# NT_MCUModule2.net
KiCad netlist of a schematic drawn in EAGLE
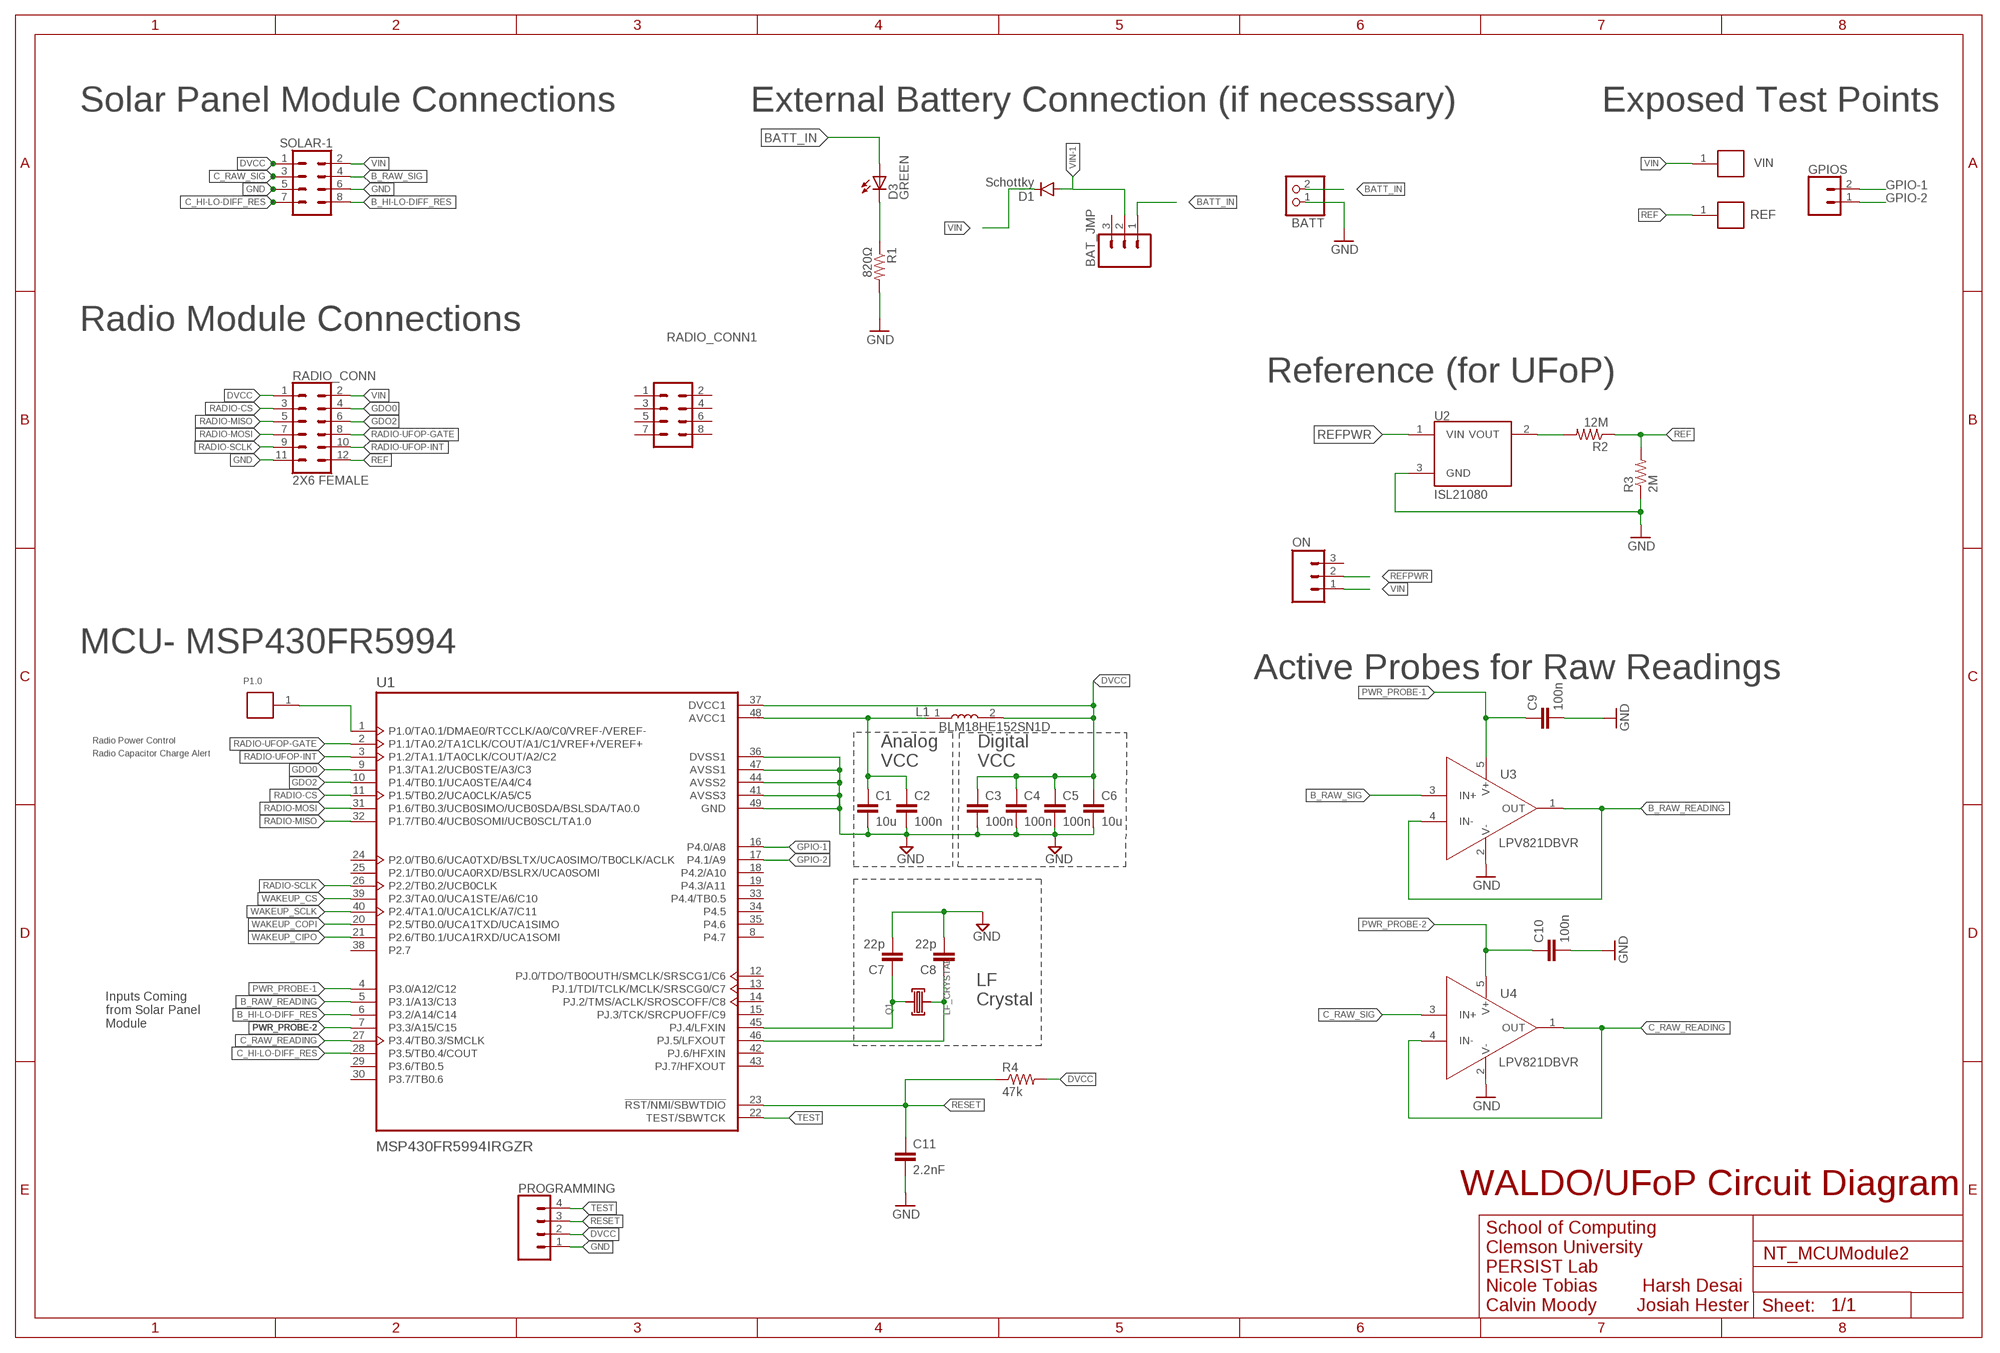
[diagram p0: schematic, sheet 1]

(export (version "E")
  (design (tool "Eeschema 10.0.6"))
  (components
    (comp (ref "BATT")
      (value "PINHD-1X2")
      (footprint "eagle-import:1X02")
      (libsource (lib "eagle-import") (part "PINHD-1X2"))
    )
    (comp (ref "BAT_JMP")
      (value "M03")
      (footprint "eagle-import:1X03-1.27MM")
      (libsource (lib "eagle-import") (part "M03"))
    )
    (comp (ref "C1")
      (value "10u")
      (footprint "eagle-import:C0603")
      (libsource (lib "eagle-import") (part "C-EUC0603"))
    )
    (comp (ref "C2")
      (value "100n")
      (footprint "eagle-import:C0603")
      (libsource (lib "eagle-import") (part "C-EUC0603"))
    )
    (comp (ref "C3")
      (value "100n")
      (footprint "eagle-import:C0603")
      (libsource (lib "eagle-import") (part "C-EUC0603"))
    )
    (comp (ref "C4")
      (value "100n")
      (footprint "eagle-import:C0603")
      (libsource (lib "eagle-import") (part "C-EUC0603"))
    )
    (comp (ref "C5")
      (value "100n")
      (footprint "eagle-import:C0603")
      (libsource (lib "eagle-import") (part "C-EUC0603"))
    )
    (comp (ref "C6")
      (value "10u")
      (footprint "eagle-import:C0603")
      (libsource (lib "eagle-import") (part "C-EUC0603"))
    )
    (comp (ref "C7")
      (value "22p")
      (footprint "eagle-import:C0603")
      (libsource (lib "eagle-import") (part "C-EUC0603"))
    )
    (comp (ref "C8")
      (value "22p")
      (footprint "eagle-import:C0603")
      (libsource (lib "eagle-import") (part "C-EUC0603"))
    )
    (comp (ref "C9")
      (value "100n")
      (footprint "eagle-import:C0603")
      (libsource (lib "eagle-import") (part "C-EUC0603"))
    )
    (comp (ref "C10")
      (value "100n")
      (footprint "eagle-import:C0603")
      (libsource (lib "eagle-import") (part "C-EUC0603"))
    )
    (comp (ref "C11")
      (value "2.2nF")
      (footprint "eagle-import:C0603")
      (libsource (lib "eagle-import") (part "C-EUC0603"))
    )
    (comp (ref "D1")
      (value "Schottky")
      (footprint "eagle-import:SOD523")
      (libsource (lib "eagle-import") (part "DIODESOD523"))
    )
    (comp (ref "D3")
      (value "GREEN")
      (footprint "eagle-import:CHIP-LED0805")
      (libsource (lib "eagle-import") (part "LEDCHIP-LED0805"))
    )
    (comp (ref "GPIOS")
      (value "CONN_02")
      (footprint "eagle-import:1X02")
      (libsource (lib "eagle-import") (part "CONN_02"))
    )
    (comp (ref "L1")
      (value "BLM18HE152SN1D")
      (footprint "eagle-import:INDC1608X95")
      (fields (field (name "DIGI-KEY_PART_NUMBER") "490-5216-1-ND") (field (name "MF") "Murata"))
      (libsource (lib "eagle-import") (part "BLM18HE152SN1D"))
    )
    (comp (ref "ON")
      (value "M03")
      (footprint "eagle-import:1X03-1.27MM")
      (libsource (lib "eagle-import") (part "M03"))
    )
    (comp (ref "P1.0")
      (value "RCU-0C")
      (footprint "eagle-import:TE_RCU-0C")
      (fields
        (field (name "COMMENT") "RCU-0C _1625854-3_")
        (field (name "MF") "TE Connectivity")
        (field (name "TOLERANCE") "0%")
      )
      (libsource (lib "eagle-import") (part "RCU-0C"))
    )
    (comp (ref "PROGRAMMING")
      (value "CONN_04")
      (footprint "eagle-import:1X04")
      (libsource (lib "eagle-import") (part "CONN_04"))
    )
    (comp (ref "Q1")
      (value "LF_CRYSTAL")
      (footprint "eagle-import:LF_CRYSTAL")
      (libsource (lib "eagle-import") (part "LF_CRYSTAL"))
    )
    (comp (ref "R1")
      (value "820Ω")
      (footprint "eagle-import:0603-RES")
      (libsource (lib "eagle-import") (part "RESISTOR0603"))
    )
    (comp (ref "R2")
      (value "12M")
      (footprint "eagle-import:0603-RES")
      (libsource (lib "eagle-import") (part "RESISTOR0603-RES"))
    )
    (comp (ref "R3")
      (value "2M")
      (footprint "eagle-import:0603-RES")
      (libsource (lib "eagle-import") (part "RESISTOR0603-RES"))
    )
    (comp (ref "R4")
      (value "47k")
      (footprint "eagle-import:0603-RES")
      (libsource (lib "eagle-import") (part "RESISTOR0603-RES"))
    )
    (comp (ref "RADIO_CONN")
      (value "2X6 FEMALE")
      (footprint "eagle-import:2X6")
      (libsource (lib "eagle-import") (part "CONN_06X2PTH_FEMALE"))
    )
    (comp (ref "RADIO_CONN1")
      (value "2X6 FEMALE")
      (footprint "eagle-import:2X4")
      (libsource (lib "eagle-import") (part "M04X2"))
    )
    (comp (ref "REF")
      (value "RCU-0C")
      (footprint "eagle-import:TE_RCU-0C")
      (fields
        (field (name "COMMENT") "RCU-0C _1625854-3_")
        (field (name "MF") "TE Connectivity")
        (field (name "TOLERANCE") "0%")
      )
      (libsource (lib "eagle-import") (part "RCU-0C"))
    )
    (comp (ref "SOLAR-1")
      (value "CONN_04X2")
      (footprint "eagle-import:2X4")
      (libsource (lib "eagle-import") (part "CONN_04X2"))
    )
    (comp (ref "U1")
      (value "MSP430FR5994IRGZR")
      (footprint "eagle-import:QFN50P700X700X100-49N")
      (fields (field (name "MF") "Texas Instruments"))
      (libsource (lib "eagle-import") (part "MSP430FR5994IRGZR"))
    )
    (comp (ref "U2")
      (value "ISL21080")
      (footprint "eagle-import:SOT-23")
      (libsource (lib "eagle-import") (part "ISL21080"))
    )
    (comp (ref "U3")
      (value "LPV821DBVR")
      (footprint "eagle-import:SOT95P280X145-5N")
      (fields (field (name "DIGI-KEY_PART_NUMBER") "296-47911-1-ND") (field (name "MF") "Texas Instruments"))
      (libsource (lib "eagle-import") (part "LPV821DBVR"))
    )
    (comp (ref "U4")
      (value "LPV821DBVR")
      (footprint "eagle-import:SOT95P280X145-5N")
      (fields (field (name "DIGI-KEY_PART_NUMBER") "296-47911-1-ND") (field (name "MF") "Texas Instruments"))
      (libsource (lib "eagle-import") (part "LPV821DBVR"))
    )
    (comp (ref "VIN")
      (value "RCU-0C")
      (footprint "eagle-import:TE_RCU-0C")
      (fields
        (field (name "COMMENT") "RCU-0C _1625854-3_")
        (field (name "MF") "TE Connectivity")
        (field (name "TOLERANCE") "0%")
      )
      (libsource (lib "eagle-import") (part "RCU-0C"))
    )
  )
  (nets
    (net (code "1") (name "BATT_IN") (class "Default")
      (node (ref "BATT") (pin "2") (pinfunction "2_2") (pintype "passive"))
      (node (ref "BAT_JMP") (pin "1") (pinfunction "1_1") (pintype "passive"))
      (node (ref "D3") (pin "A") (pinfunction "A_A") (pintype "passive"))
    )
    (net (code "2") (name "B_HI-LO-DIFF_RES") (class "Default")
      (node (ref "SOLAR-1") (pin "8") (pinfunction "8_8") (pintype "passive"))
      (node (ref "U1") (pin "6") (pinfunction "P3.2/A14/C14_6") (pintype "bidirectional"))
    )
    (net (code "3") (name "B_RAW_READING") (class "Default")
      (node (ref "U1") (pin "5") (pinfunction "P3.1/A13/C13_5") (pintype "bidirectional"))
      (node (ref "U3") (pin "1") (pinfunction "OUT_1") (pintype "output"))
      (node (ref "U3") (pin "4") (pinfunction "IN-_4") (pintype "input"))
    )
    (net (code "4") (name "B_RAW_SIG") (class "Default")
      (node (ref "SOLAR-1") (pin "4") (pinfunction "4_4") (pintype "passive"))
      (node (ref "U3") (pin "3") (pinfunction "IN+_3") (pintype "input"))
    )
    (net (code "5") (name "C_HI-LO-DIFF_RES") (class "Default")
      (node (ref "SOLAR-1") (pin "7") (pinfunction "7_7") (pintype "passive"))
      (node (ref "U1") (pin "28") (pinfunction "P3.5/TB0.4/COUT_28") (pintype "bidirectional"))
    )
    (net (code "6") (name "C_RAW_READING") (class "Default")
      (node (ref "U1") (pin "27") (pinfunction "P3.4/TB0.3/SMCLK_27") (pintype "bidirectional"))
      (node (ref "U4") (pin "1") (pinfunction "OUT_1") (pintype "output"))
      (node (ref "U4") (pin "4") (pinfunction "IN-_4") (pintype "input"))
    )
    (net (code "7") (name "C_RAW_SIG") (class "Default")
      (node (ref "SOLAR-1") (pin "3") (pinfunction "3_3") (pintype "passive"))
      (node (ref "U4") (pin "3") (pinfunction "IN+_3") (pintype "input"))
    )
    (net (code "8") (name "DVCC") (class "Default")
      (node (ref "C3") (pin "1") (pinfunction "1_1") (pintype "passive"))
      (node (ref "C4") (pin "1") (pinfunction "1_1") (pintype "passive"))
      (node (ref "C5") (pin "1") (pinfunction "1_1") (pintype "passive"))
      (node (ref "C6") (pin "1") (pinfunction "1_1") (pintype "passive"))
      (node (ref "L1") (pin "2") (pinfunction "2_2") (pintype "passive"))
      (node (ref "PROGRAMMING") (pin "2") (pinfunction "2_2") (pintype "passive"))
      (node (ref "R4") (pin "2") (pinfunction "2_2") (pintype "passive"))
      (node (ref "RADIO_CONN") (pin "1") (pinfunction "1_1") (pintype "passive"))
      (node (ref "SOLAR-1") (pin "1") (pinfunction "1_1") (pintype "passive"))
      (node (ref "U1") (pin "37") (pinfunction "DVCC1_37") (pintype "power_in"))
    )
    (net (code "9") (name "GDO0") (class "Default")
      (node (ref "RADIO_CONN") (pin "4") (pinfunction "4_4") (pintype "passive"))
      (node (ref "U1") (pin "9") (pinfunction "P1.3/TA1.2/UCB0STE/A3/C3_9") (pintype "bidirectional"))
    )
    (net (code "10") (name "GDO2") (class "Default")
      (node (ref "RADIO_CONN") (pin "6") (pinfunction "6_6") (pintype "passive"))
      (node (ref "U1") (pin "10") (pinfunction "P1.4/TB0.1/UCA0STE/A4/C4_10") (pintype "bidirectional"))
    )
    (net (code "11") (name "GND") (class "Default")
      (node (ref "BATT") (pin "1") (pinfunction "1_1") (pintype "passive"))
      (node (ref "C1") (pin "2") (pinfunction "2_2") (pintype "passive"))
      (node (ref "C10") (pin "2") (pinfunction "2_2") (pintype "passive"))
      (node (ref "C11") (pin "2") (pinfunction "2_2") (pintype "passive"))
      (node (ref "C2") (pin "2") (pinfunction "2_2") (pintype "passive"))
      (node (ref "C3") (pin "2") (pinfunction "2_2") (pintype "passive"))
      (node (ref "C4") (pin "2") (pinfunction "2_2") (pintype "passive"))
      (node (ref "C5") (pin "2") (pinfunction "2_2") (pintype "passive"))
      (node (ref "C6") (pin "2") (pinfunction "2_2") (pintype "passive"))
      (node (ref "C7") (pin "2") (pinfunction "2_2") (pintype "passive"))
      (node (ref "C8") (pin "2") (pinfunction "2_2") (pintype "passive"))
      (node (ref "C9") (pin "2") (pinfunction "2_2") (pintype "passive"))
      (node (ref "PROGRAMMING") (pin "1") (pinfunction "1_1") (pintype "passive"))
      (node (ref "R1") (pin "2") (pinfunction "2_2") (pintype "passive"))
      (node (ref "R3") (pin "1") (pinfunction "1_1") (pintype "passive"))
      (node (ref "RADIO_CONN") (pin "11") (pinfunction "11_11") (pintype "passive"))
      (node (ref "SOLAR-1") (pin "5") (pinfunction "5_5") (pintype "passive"))
      (node (ref "SOLAR-1") (pin "6") (pinfunction "6_6") (pintype "passive"))
      (node (ref "U1") (pin "36") (pinfunction "DVSS1_36") (pintype "power_in"))
      (node (ref "U1") (pin "41") (pinfunction "AVSS3_41") (pintype "power_in"))
      (node (ref "U1") (pin "44") (pinfunction "AVSS2_44") (pintype "power_in"))
      (node (ref "U1") (pin "47") (pinfunction "AVSS1_47") (pintype "power_in"))
      (node (ref "U1") (pin "49") (pinfunction "GND_49") (pintype "power_in"))
      (node (ref "U2") (pin "3") (pinfunction "GND_3") (pintype "bidirectional"))
      (node (ref "U3") (pin "2") (pinfunction "V-_2") (pintype "power_in"))
      (node (ref "U4") (pin "2") (pinfunction "V-_2") (pintype "power_in"))
    )
    (net (code "12") (name "GPIO-1") (class "Default")
      (node (ref "GPIOS") (pin "2") (pinfunction "2_2") (pintype "passive"))
      (node (ref "U1") (pin "16") (pinfunction "P4.0/A8_16") (pintype "bidirectional"))
    )
    (net (code "13") (name "GPIO-2") (class "Default")
      (node (ref "GPIOS") (pin "1") (pinfunction "1_1") (pintype "passive"))
      (node (ref "U1") (pin "17") (pinfunction "P4.1/A9_17") (pintype "bidirectional"))
    )
    (net (code "14") (name "Net-(D3-PadC)") (class "Default")
      (node (ref "D3") (pin "C") (pinfunction "C_C") (pintype "passive"))
      (node (ref "R1") (pin "1") (pinfunction "1_1") (pintype "passive"))
    )
    (net (code "15") (name "Net-(U1-AVCC1)") (class "Default")
      (node (ref "C1") (pin "1") (pinfunction "1_1") (pintype "passive"))
      (node (ref "C2") (pin "1") (pinfunction "1_1") (pintype "passive"))
      (node (ref "L1") (pin "1") (pinfunction "1_1") (pintype "passive"))
      (node (ref "U1") (pin "48") (pinfunction "AVCC1_48") (pintype "power_in"))
    )
    (net (code "16") (name "Net-(U1-P1.0{slash}TA0.1{slash}DMAE0{slash}RTCCLK{slash}A0{slash}C0{slash}VREF-{slash}VEREF-)") (class "Default")
      (node (ref "P1.0") (pin "1") (pinfunction "1_1") (pintype "passive"))
      (node (ref "U1") (pin "1") (pinfunction "P1.0/TA0.1/DMAE0/RTCCLK/A0/C0/VREF-/VEREF-_1") (pintype "bidirectional"))
    )
    (net (code "17") (name "Net-(U1-PJ.4{slash}LFXIN)") (class "Default")
      (node (ref "C7") (pin "1") (pinfunction "1_1") (pintype "passive"))
      (node (ref "Q1") (pin "1") (pinfunction "1_1") (pintype "bidirectional"))
      (node (ref "U1") (pin "45") (pinfunction "PJ.4/LFXIN_45") (pintype "bidirectional"))
    )
    (net (code "18") (name "Net-(U1-PJ.5{slash}LFXOUT)") (class "Default")
      (node (ref "C8") (pin "1") (pinfunction "1_1") (pintype "passive"))
      (node (ref "Q1") (pin "2") (pinfunction "2_2") (pintype "bidirectional"))
      (node (ref "U1") (pin "46") (pinfunction "PJ.5/LFXOUT_46") (pintype "bidirectional"))
    )
    (net (code "19") (name "Net-(U2-VOUT)") (class "Default")
      (node (ref "R2") (pin "2") (pinfunction "2_2") (pintype "passive"))
      (node (ref "U2") (pin "2") (pinfunction "VOUT_2") (pintype "bidirectional"))
    )
    (net (code "20") (name "PWR_PROBE-1") (class "Default")
      (node (ref "C9") (pin "1") (pinfunction "1_1") (pintype "passive"))
      (node (ref "U1") (pin "4") (pinfunction "P3.0/A12/C12_4") (pintype "bidirectional"))
      (node (ref "U3") (pin "5") (pinfunction "V+_5") (pintype "power_in"))
    )
    (net (code "21") (name "PWR_PROBE-2") (class "Default")
      (node (ref "C10") (pin "1") (pinfunction "1_1") (pintype "passive"))
      (node (ref "U1") (pin "7") (pinfunction "P3.3/A15/C15_7") (pintype "bidirectional"))
      (node (ref "U4") (pin "5") (pinfunction "V+_5") (pintype "power_in"))
    )
    (net (code "22") (name "RADIO-CS") (class "Default")
      (node (ref "RADIO_CONN") (pin "3") (pinfunction "3_3") (pintype "passive"))
      (node (ref "U1") (pin "11") (pinfunction "P1.5/TB0.2/UCA0CLK/A5/C5_11") (pintype "bidirectional"))
    )
    (net (code "23") (name "RADIO-MISO") (class "Default")
      (node (ref "RADIO_CONN") (pin "5") (pinfunction "5_5") (pintype "passive"))
      (node (ref "U1") (pin "32") (pinfunction "P1.7/TB0.4/UCB0SOMI/UCB0SCL/TA1.0_32") (pintype "bidirectional"))
    )
    (net (code "24") (name "RADIO-MOSI") (class "Default")
      (node (ref "RADIO_CONN") (pin "7") (pinfunction "7_7") (pintype "passive"))
      (node (ref "U1") (pin "31") (pinfunction "P1.6/TB0.3/UCB0SIMO/UCB0SDA/BSLSDA/TA0.0_31") (pintype "bidirectional"))
    )
    (net (code "25") (name "RADIO-SCLK") (class "Default")
      (node (ref "RADIO_CONN") (pin "9") (pinfunction "9_9") (pintype "passive"))
      (node (ref "U1") (pin "26") (pinfunction "P2.2/TB0.2/UCB0CLK_26") (pintype "bidirectional"))
    )
    (net (code "26") (name "RADIO-UFOP-GATE") (class "Default")
      (node (ref "RADIO_CONN") (pin "8") (pinfunction "8_8") (pintype "passive"))
      (node (ref "U1") (pin "2") (pinfunction "P1.1/TA0.2/TA1CLK/COUT/A1/C1/VREF+/VEREF+_2") (pintype "bidirectional"))
    )
    (net (code "27") (name "RADIO-UFOP-INT") (class "Default")
      (node (ref "RADIO_CONN") (pin "10") (pinfunction "10_10") (pintype "passive"))
      (node (ref "U1") (pin "3") (pinfunction "P1.2/TA1.1/TA0CLK/COUT/A2/C2_3") (pintype "bidirectional"))
    )
    (net (code "28") (name "REF") (class "Default")
      (node (ref "R2") (pin "1") (pinfunction "1_1") (pintype "passive"))
      (node (ref "R3") (pin "2") (pinfunction "2_2") (pintype "passive"))
      (node (ref "RADIO_CONN") (pin "12") (pinfunction "12_12") (pintype "passive"))
      (node (ref "REF") (pin "1") (pinfunction "1_1") (pintype "passive"))
    )
    (net (code "29") (name "REFPWR") (class "Default")
      (node (ref "ON") (pin "2") (pinfunction "2_2") (pintype "passive"))
      (node (ref "U2") (pin "1") (pinfunction "VIN_1") (pintype "bidirectional"))
    )
    (net (code "30") (name "RESET") (class "Default")
      (node (ref "C11") (pin "1") (pinfunction "1_1") (pintype "passive"))
      (node (ref "PROGRAMMING") (pin "3") (pinfunction "3_3") (pintype "passive"))
      (node (ref "R4") (pin "1") (pinfunction "1_1") (pintype "passive"))
      (node (ref "U1") (pin "23") (pinfunction "~{RST/NMI/SBWTDIO}_23") (pintype "bidirectional"))
    )
    (net (code "31") (name "TEST") (class "Default")
      (node (ref "PROGRAMMING") (pin "4") (pinfunction "4_4") (pintype "passive"))
      (node (ref "U1") (pin "22") (pinfunction "TEST/SBWTCK_22") (pintype "bidirectional"))
    )
    (net (code "32") (name "VIN") (class "Default")
      (node (ref "D1") (pin "C") (pinfunction "C_C") (pintype "passive"))
      (node (ref "ON") (pin "1") (pinfunction "1_1") (pintype "passive"))
      (node (ref "RADIO_CONN") (pin "2") (pinfunction "2_2") (pintype "passive"))
      (node (ref "SOLAR-1") (pin "2") (pinfunction "2_2") (pintype "passive"))
      (node (ref "VIN") (pin "1") (pinfunction "1_1") (pintype "passive"))
    )
    (net (code "33") (name "VIN-1") (class "Default")
      (node (ref "BAT_JMP") (pin "2") (pinfunction "2_2") (pintype "passive"))
      (node (ref "D1") (pin "A") (pinfunction "A_A") (pintype "passive"))
    )
    (net (code "34") (name "WAKEUP_CIPO") (class "Default")
      (node (ref "U1") (pin "21") (pinfunction "P2.6/TB0.1/UCA1RXD/UCA1SOMI_21") (pintype "bidirectional"))
    )
    (net (code "35") (name "WAKEUP_COPI") (class "Default")
      (node (ref "U1") (pin "20") (pinfunction "P2.5/TB0.0/UCA1TXD/UCA1SIMO_20") (pintype "bidirectional"))
    )
    (net (code "36") (name "WAKEUP_CS") (class "Default")
      (node (ref "U1") (pin "39") (pinfunction "P2.3/TA0.0/UCA1STE/A6/C10_39") (pintype "bidirectional"))
    )
    (net (code "37") (name "WAKEUP_SCLK") (class "Default")
      (node (ref "U1") (pin "40") (pinfunction "P2.4/TA1.0/UCA1CLK/A7/C11_40") (pintype "bidirectional"))
    )
    (net (code "38") (name "unconnected-(BAT_JMP-Pad3)") (class "Default")
      (node (ref "BAT_JMP") (pin "3") (pinfunction "3_3") (pintype "passive"))
    )
    (net (code "39") (name "unconnected-(ON-Pad3)") (class "Default")
      (node (ref "ON") (pin "3") (pinfunction "3_3") (pintype "passive"))
    )
    (net (code "40") (name "unconnected-(RADIO_CONN1-Pad1)") (class "Default")
      (node (ref "RADIO_CONN1") (pin "1") (pinfunction "1_1") (pintype "passive"))
    )
    (net (code "41") (name "unconnected-(RADIO_CONN1-Pad2)") (class "Default")
      (node (ref "RADIO_CONN1") (pin "2") (pinfunction "2_2") (pintype "passive"))
    )
    (net (code "42") (name "unconnected-(RADIO_CONN1-Pad3)") (class "Default")
      (node (ref "RADIO_CONN1") (pin "3") (pinfunction "3_3") (pintype "passive"))
    )
    (net (code "43") (name "unconnected-(RADIO_CONN1-Pad4)") (class "Default")
      (node (ref "RADIO_CONN1") (pin "4") (pinfunction "4_4") (pintype "passive"))
    )
    (net (code "44") (name "unconnected-(RADIO_CONN1-Pad5)") (class "Default")
      (node (ref "RADIO_CONN1") (pin "5") (pinfunction "5_5") (pintype "passive"))
    )
    (net (code "45") (name "unconnected-(RADIO_CONN1-Pad6)") (class "Default")
      (node (ref "RADIO_CONN1") (pin "6") (pinfunction "6_6") (pintype "passive"))
    )
    (net (code "46") (name "unconnected-(RADIO_CONN1-Pad7)") (class "Default")
      (node (ref "RADIO_CONN1") (pin "7") (pinfunction "7_7") (pintype "passive"))
    )
    (net (code "47") (name "unconnected-(RADIO_CONN1-Pad8)") (class "Default")
      (node (ref "RADIO_CONN1") (pin "8") (pinfunction "8_8") (pintype "passive"))
    )
    (net (code "48") (name "unconnected-(U1-P2.0{slash}TB0.6{slash}UCA0TXD{slash}BSLTX{slash}UCA0SIMO{slash}TB0CLK{slash}ACLK-Pad24)") (class "Default")
      (node (ref "U1") (pin "24") (pinfunction "P2.0/TB0.6/UCA0TXD/BSLTX/UCA0SIMO/TB0CLK/ACLK_24") (pintype "bidirectional"))
    )
    (net (code "49") (name "unconnected-(U1-P2.1{slash}TB0.0{slash}UCA0RXD{slash}BSLRX{slash}UCA0SOMI-Pad25)") (class "Default")
      (node (ref "U1") (pin "25") (pinfunction "P2.1/TB0.0/UCA0RXD/BSLRX/UCA0SOMI_25") (pintype "bidirectional"))
    )
    (net (code "50") (name "unconnected-(U1-P2.7-Pad38)") (class "Default")
      (node (ref "U1") (pin "38") (pinfunction "P2.7_38") (pintype "bidirectional"))
    )
    (net (code "51") (name "unconnected-(U1-P3.6{slash}TB0.5-Pad29)") (class "Default")
      (node (ref "U1") (pin "29") (pinfunction "P3.6/TB0.5_29") (pintype "bidirectional"))
    )
    (net (code "52") (name "unconnected-(U1-P3.7{slash}TB0.6-Pad30)") (class "Default")
      (node (ref "U1") (pin "30") (pinfunction "P3.7/TB0.6_30") (pintype "bidirectional"))
    )
    (net (code "53") (name "unconnected-(U1-P4.2{slash}A10-Pad18)") (class "Default")
      (node (ref "U1") (pin "18") (pinfunction "P4.2/A10_18") (pintype "bidirectional"))
    )
    (net (code "54") (name "unconnected-(U1-P4.3{slash}A11-Pad19)") (class "Default")
      (node (ref "U1") (pin "19") (pinfunction "P4.3/A11_19") (pintype "bidirectional"))
    )
    (net (code "55") (name "unconnected-(U1-P4.4{slash}TB0.5-Pad33)") (class "Default")
      (node (ref "U1") (pin "33") (pinfunction "P4.4/TB0.5_33") (pintype "bidirectional"))
    )
    (net (code "56") (name "unconnected-(U1-P4.5-Pad34)") (class "Default")
      (node (ref "U1") (pin "34") (pinfunction "P4.5_34") (pintype "bidirectional"))
    )
    (net (code "57") (name "unconnected-(U1-P4.6-Pad35)") (class "Default")
      (node (ref "U1") (pin "35") (pinfunction "P4.6_35") (pintype "bidirectional"))
    )
    (net (code "58") (name "unconnected-(U1-P4.7-Pad8)") (class "Default")
      (node (ref "U1") (pin "8") (pinfunction "P4.7_8") (pintype "bidirectional"))
    )
    (net (code "59") (name "unconnected-(U1-PJ.0{slash}TDO{slash}TB0OUTH{slash}SMCLK{slash}SRSCG1{slash}C6-Pad12)") (class "Default")
      (node (ref "U1") (pin "12") (pinfunction "PJ.0/TDO/TB0OUTH/SMCLK/SRSCG1/C6_12") (pintype "bidirectional"))
    )
    (net (code "60") (name "unconnected-(U1-PJ.1{slash}TDI{slash}TCLK{slash}MCLK{slash}SRSCG0{slash}C7-Pad13)") (class "Default")
      (node (ref "U1") (pin "13") (pinfunction "PJ.1/TDI/TCLK/MCLK/SRSCG0/C7_13") (pintype "bidirectional"))
    )
    (net (code "61") (name "unconnected-(U1-PJ.2{slash}TMS{slash}ACLK{slash}SROSCOFF{slash}C8-Pad14)") (class "Default")
      (node (ref "U1") (pin "14") (pinfunction "PJ.2/TMS/ACLK/SROSCOFF/C8_14") (pintype "bidirectional"))
    )
    (net (code "62") (name "unconnected-(U1-PJ.3{slash}TCK{slash}SRCPUOFF{slash}C9-Pad15)") (class "Default")
      (node (ref "U1") (pin "15") (pinfunction "PJ.3/TCK/SRCPUOFF/C9_15") (pintype "bidirectional"))
    )
    (net (code "63") (name "unconnected-(U1-PJ.6{slash}HFXIN-Pad42)") (class "Default")
      (node (ref "U1") (pin "42") (pinfunction "PJ.6/HFXIN_42") (pintype "bidirectional"))
    )
    (net (code "64") (name "unconnected-(U1-PJ.7{slash}HFXOUT-Pad43)") (class "Default")
      (node (ref "U1") (pin "43") (pinfunction "PJ.7/HFXOUT_43") (pintype "bidirectional"))
    )
  )
)
